# Fri3D_2024_Power.net
KiCad netlist of a schematic drawn in Altium Designer
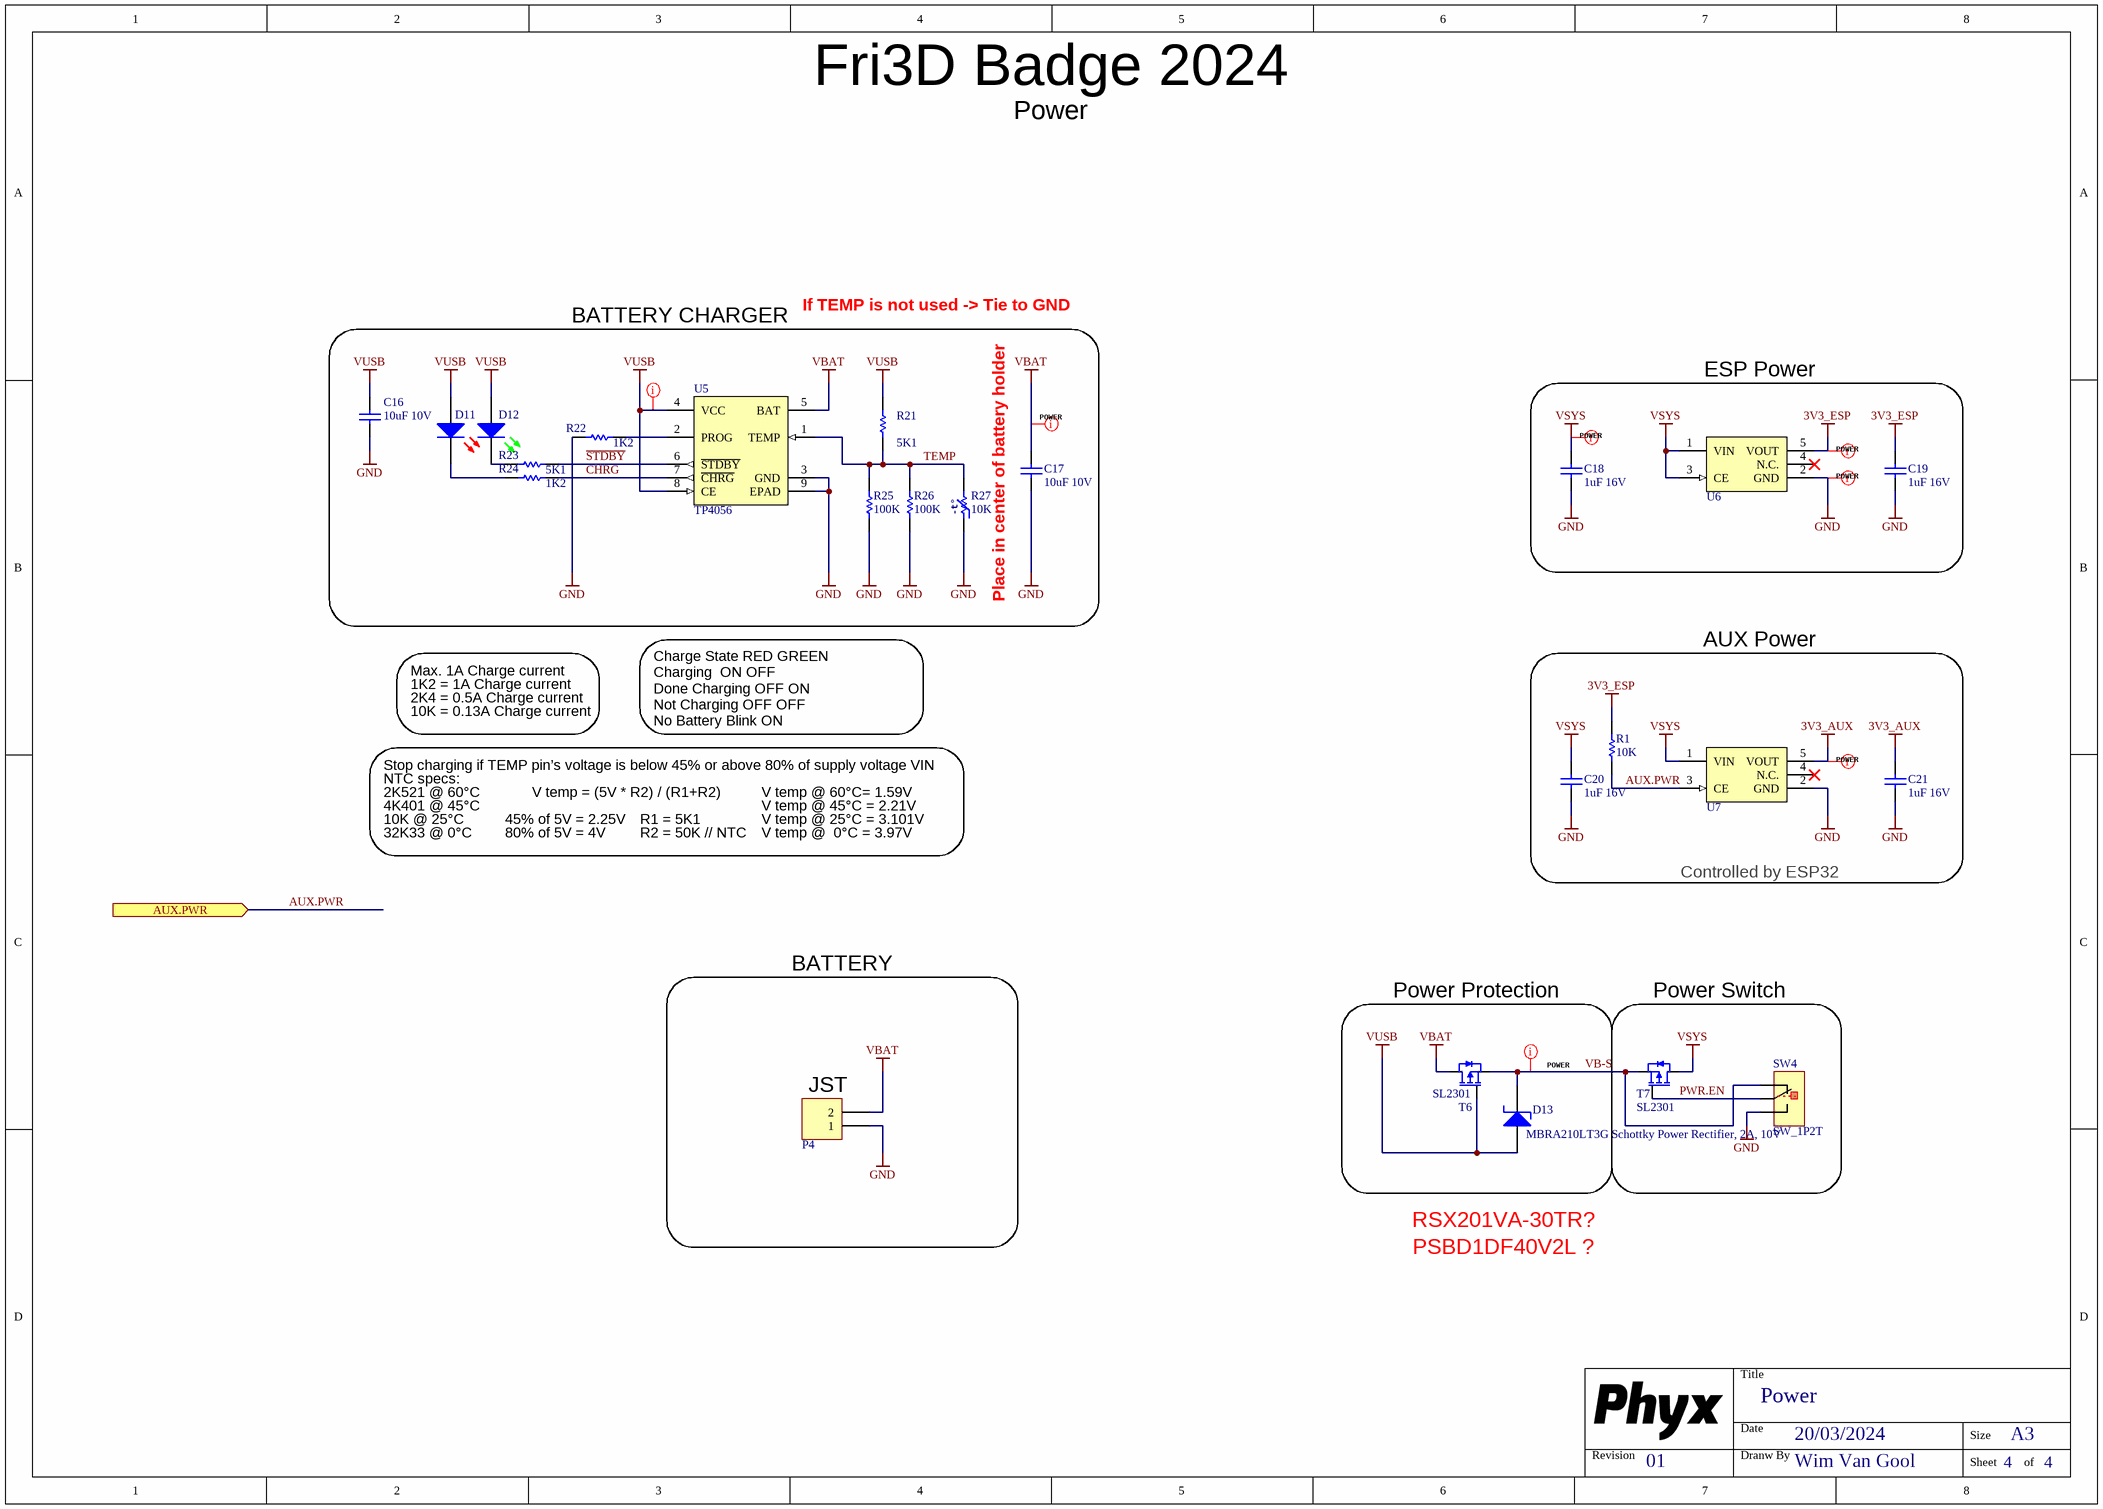
[diagram p0: Fri3D_2024_Power.SchDoc]

(export (version "E")
  (design (tool "Eeschema 10.0.6"))
  (components
    (comp (ref "C16")
      (value "10uF 10V")
      (footprint "C0805_N")
      (description "Capacitor Ceramic")
      (fields (field (name "Comment") "CAP_CERAMIC"))
      (libsource (lib "Phyx_Components") (part "CAP_CERAMIC"))
    )
    (comp (ref "C17")
      (value "10uF 10V")
      (footprint "C0805_N")
      (description "Capacitor Ceramic")
      (fields (field (name "Comment") "CAP_CERAMIC"))
      (libsource (lib "Phyx_Components") (part "CAP_CERAMIC"))
    )
    (comp (ref "C18")
      (value "1uF 16V")
      (footprint "C0603_N")
      (description "Capacitor Ceramic")
      (fields (field (name "Comment") "CAP_CERAMIC"))
      (libsource (lib "Phyx_Components") (part "CAP_CERAMIC"))
    )
    (comp (ref "C19")
      (value "1uF 16V")
      (footprint "C0603_N")
      (description "Capacitor Ceramic")
      (fields (field (name "Comment") "CAP_CERAMIC"))
      (libsource (lib "Phyx_Components") (part "CAP_CERAMIC"))
    )
    (comp (ref "C20")
      (value "1uF 16V")
      (footprint "C0603_N")
      (description "Capacitor Ceramic")
      (fields (field (name "Comment") "CAP_CERAMIC"))
      (libsource (lib "Phyx_Components") (part "CAP_CERAMIC"))
    )
    (comp (ref "C21")
      (value "1uF 16V")
      (footprint "C0603_N")
      (description "Capacitor Ceramic")
      (fields (field (name "Comment") "CAP_CERAMIC"))
      (libsource (lib "Phyx_Components") (part "CAP_CERAMIC"))
    )
    (comp (ref "D11")
      (value "Default 0805 Red LED")
      (footprint "LED_0805_RD")
      (description "=Description")
      (libsource (lib "Phyx_Components") (part "LED_RED"))
    )
    (comp (ref "D12")
      (value "Default 0805 Green LED")
      (footprint "LED_0805_GR")
      (description "=Description")
      (libsource (lib "Phyx_Components") (part "LED_GREEN"))
    )
    (comp (ref "D13")
      (value "MBRA210LT3G Schottky Power Rectifier, 2A, 10V")
      (footprint "SMA_AC")
      (description "=Description")
      (libsource (lib "Phyx_Components") (part "Schottky_AC"))
    )
    (comp (ref "P4")
      (value "Header RA 1.5mm Shrouded S2B-ZR-SM4A-TF")
      (footprint "JST_ZH_S2B-ZR-SM4A-TF")
      (libsource (lib "Phyx_Components") (part "Header 2"))
    )
    (comp (ref "R1")
      (value "10K")
      (footprint "R0603_N")
      (fields (field (name "Comment") "RESISTOR"))
      (libsource (lib "Phyx_Components") (part "RESISTOR"))
    )
    (comp (ref "R21")
      (value "5K1")
      (footprint "R0603_N")
      (fields (field (name "Comment") "RESISTOR"))
      (libsource (lib "Phyx_Components") (part "RESISTOR"))
    )
    (comp (ref "R22")
      (value "1K2")
      (footprint "R0603_N")
      (fields (field (name "Comment") "RESISTOR"))
      (libsource (lib "Phyx_Components") (part "RESISTOR"))
    )
    (comp (ref "R23")
      (value "5K1")
      (footprint "R0603_N")
      (fields (field (name "Comment") "RESISTOR"))
      (libsource (lib "Phyx_Components") (part "RESISTOR"))
    )
    (comp (ref "R24")
      (value "1K2")
      (footprint "R0603_N")
      (fields (field (name "Comment") "RESISTOR"))
      (libsource (lib "Phyx_Components") (part "RESISTOR"))
    )
    (comp (ref "R25")
      (value "100K")
      (footprint "R0603_N")
      (fields (field (name "Comment") "RESISTOR"))
      (libsource (lib "Phyx_Components") (part "RESISTOR"))
    )
    (comp (ref "R26")
      (value "100K")
      (footprint "R0603_N")
      (fields (field (name "Comment") "RESISTOR"))
      (libsource (lib "Phyx_Components") (part "RESISTOR"))
    )
    (comp (ref "R27")
      (value "10K")
      (footprint "R0402")
      (fields (field (name "Comment") "NTC"))
      (libsource (lib "Phyx_Components") (part "RESISTOR_NTC"))
    )
    (comp (ref "SW4")
      (value "SW_1P2T")
      (footprint "WE_450404015514")
      (libsource (lib "Phyx_Components") (part "SW_1P2T"))
    )
    (comp (ref "T6")
      (value "SL2301")
      (footprint "SOT23-3")
      (description "=Description")
      (fields (field (name "Comment") "-2.3A -20V P-Ch MOSFET Vgs -1V"))
      (libsource (lib "Phyx_Components") (part "P_MOSFET_GSD"))
    )
    (comp (ref "T7")
      (value "SL2301")
      (footprint "SOT23-3")
      (description "=Description")
      (fields (field (name "Comment") "-2.3A -20V P-Ch MOSFET Vgs -1V"))
      (libsource (lib "Phyx_Components") (part "P_MOSFET_GSD"))
    )
    (comp (ref "U5")
      (value "TP4056")
      (footprint "SOIC_N_8_TH")
      (description "=Description")
      (fields (field (name "Comment") "Single Cell LiIon charger max 1A"))
      (libsource (lib "Phyx_Components") (part "TP4056"))
    )
    (comp (ref "U6")
      (value "3V3 LDO 700mA 50mV")
      (footprint "SOT23-5")
      (description "=Designator")
      (libsource (lib "Phyx_Components") (part "XC6210_SOT"))
    )
    (comp (ref "U7")
      (value "3V3 LDO 700mA 50mV")
      (footprint "SOT23-5")
      (description "=Designator")
      (libsource (lib "Phyx_Components") (part "XC6210_SOT"))
    )
  )
  (nets
    (net (code "1") (name "/AUX.PWR") (class "Default")
      (node (ref "R1") (pin "2") (pinfunction "2_2") (pintype "passive"))
      (node (ref "U7") (pin "3") (pinfunction "CE_3") (pintype "input"))
    )
    (net (code "2") (name "/PWR.EN") (class "Default")
      (node (ref "SW4") (pin "2") (pinfunction "2_2") (pintype "passive"))
      (node (ref "T7") (pin "1") (pinfunction "G_1") (pintype "passive"))
    )
    (net (code "3") (name "/TEMP") (class "Default")
      (node (ref "R21") (pin "2") (pinfunction "2_2") (pintype "passive"))
      (node (ref "R25") (pin "1") (pinfunction "1_1") (pintype "passive"))
      (node (ref "R26") (pin "1") (pinfunction "1_1") (pintype "passive"))
      (node (ref "R27") (pin "1") (pinfunction "1_1") (pintype "passive"))
      (node (ref "U5") (pin "1") (pinfunction "TEMP_1") (pintype "input"))
    )
    (net (code "4") (name "/VB-S") (class "Default")
      (node (ref "D13") (pin "C") (pinfunction "C_C") (pintype "passive"))
      (node (ref "SW4") (pin "1") (pinfunction "1_1") (pintype "passive"))
      (node (ref "T6") (pin "2") (pinfunction "S_2") (pintype "passive"))
      (node (ref "T7") (pin "2") (pinfunction "S_2") (pintype "passive"))
    )
    (net (code "5") (name "/~{CHRG}") (class "Default")
      (node (ref "R24") (pin "2") (pinfunction "2_2") (pintype "passive"))
      (node (ref "U5") (pin "7") (pinfunction "~{CHRG}_7") (pintype "output"))
    )
    (net (code "6") (name "/~{STDBY}") (class "Default")
      (node (ref "R23") (pin "2") (pinfunction "2_2") (pintype "passive"))
      (node (ref "U5") (pin "6") (pinfunction "~{STDBY}_6") (pintype "output"))
    )
    (net (code "7") (name "3V3_AUX") (class "Default")
      (node (ref "C21") (pin "1") (pinfunction "1_1") (pintype "passive"))
      (node (ref "U7") (pin "5") (pinfunction "VOUT_5") (pintype "power_in"))
    )
    (net (code "8") (name "3V3_ESP") (class "Default")
      (node (ref "C19") (pin "1") (pinfunction "1_1") (pintype "passive"))
      (node (ref "R1") (pin "1") (pinfunction "1_1") (pintype "passive"))
      (node (ref "U6") (pin "5") (pinfunction "VOUT_5") (pintype "power_in"))
    )
    (net (code "9") (name "GND") (class "Default")
      (node (ref "C16") (pin "2") (pinfunction "2_2") (pintype "passive"))
      (node (ref "C17") (pin "2") (pinfunction "2_2") (pintype "passive"))
      (node (ref "C18") (pin "2") (pinfunction "2_2") (pintype "passive"))
      (node (ref "C19") (pin "2") (pinfunction "2_2") (pintype "passive"))
      (node (ref "C20") (pin "2") (pinfunction "2_2") (pintype "passive"))
      (node (ref "C21") (pin "2") (pinfunction "2_2") (pintype "passive"))
      (node (ref "P4") (pin "1") (pinfunction "1_1") (pintype "passive"))
      (node (ref "R22") (pin "2") (pinfunction "2_2") (pintype "passive"))
      (node (ref "R25") (pin "2") (pinfunction "2_2") (pintype "passive"))
      (node (ref "R26") (pin "2") (pinfunction "2_2") (pintype "passive"))
      (node (ref "R27") (pin "2") (pinfunction "2_2") (pintype "passive"))
      (node (ref "SW4") (pin "3") (pinfunction "3_3") (pintype "passive"))
      (node (ref "U5") (pin "3") (pinfunction "GND_3") (pintype "power_in"))
      (node (ref "U5") (pin "9") (pinfunction "EPAD_9") (pintype "power_in"))
      (node (ref "U6") (pin "2") (pinfunction "GND_2") (pintype "power_in"))
      (node (ref "U7") (pin "2") (pinfunction "GND_2") (pintype "power_in"))
    )
    (net (code "10") (name "Net-(D11-K)") (class "Default")
      (node (ref "D11") (pin "2") (pinfunction "K_2") (pintype "passive"))
      (node (ref "R24") (pin "1") (pinfunction "1_1") (pintype "passive"))
    )
    (net (code "11") (name "Net-(D12-K)") (class "Default")
      (node (ref "D12") (pin "2") (pinfunction "K_2") (pintype "passive"))
      (node (ref "R23") (pin "1") (pinfunction "1_1") (pintype "passive"))
    )
    (net (code "12") (name "Net-(U5-PROG)") (class "Default")
      (node (ref "R22") (pin "1") (pinfunction "1_1") (pintype "passive"))
      (node (ref "U5") (pin "2") (pinfunction "PROG_2") (pintype "passive"))
    )
    (net (code "13") (name "VBAT") (class "Default")
      (node (ref "C17") (pin "1") (pinfunction "1_1") (pintype "passive"))
      (node (ref "P4") (pin "2") (pinfunction "2_2") (pintype "passive"))
      (node (ref "T6") (pin "3") (pinfunction "D_3") (pintype "passive"))
      (node (ref "U5") (pin "5") (pinfunction "BAT_5") (pintype "power_in"))
    )
    (net (code "14") (name "VSYS") (class "Default")
      (node (ref "C18") (pin "1") (pinfunction "1_1") (pintype "passive"))
      (node (ref "C20") (pin "1") (pinfunction "1_1") (pintype "passive"))
      (node (ref "T7") (pin "3") (pinfunction "D_3") (pintype "passive"))
      (node (ref "U6") (pin "1") (pinfunction "VIN_1") (pintype "power_in"))
      (node (ref "U6") (pin "3") (pinfunction "CE_3") (pintype "input"))
      (node (ref "U7") (pin "1") (pinfunction "VIN_1") (pintype "power_in"))
    )
    (net (code "15") (name "VUSB") (class "Default")
      (node (ref "C16") (pin "1") (pinfunction "1_1") (pintype "passive"))
      (node (ref "D11") (pin "1") (pinfunction "A_1") (pintype "passive"))
      (node (ref "D12") (pin "1") (pinfunction "A_1") (pintype "passive"))
      (node (ref "D13") (pin "A") (pinfunction "A_A") (pintype "passive"))
      (node (ref "R21") (pin "1") (pinfunction "1_1") (pintype "passive"))
      (node (ref "T6") (pin "1") (pinfunction "G_1") (pintype "passive"))
      (node (ref "U5") (pin "4") (pinfunction "VCC_4") (pintype "power_in"))
      (node (ref "U5") (pin "8") (pinfunction "CE_8") (pintype "input"))
    )
    (net (code "16") (name "unconnected-(U6-N.C.-Pad4)") (class "Default")
      (node (ref "U6") (pin "4") (pinfunction "N.C._4") (pintype "passive+no_connect"))
    )
    (net (code "17") (name "unconnected-(U7-N.C.-Pad4)") (class "Default")
      (node (ref "U7") (pin "4") (pinfunction "N.C._4") (pintype "passive+no_connect"))
    )
  )
)
